# valoohj.net
KiCad netlist of a schematic drawn in EAGLE
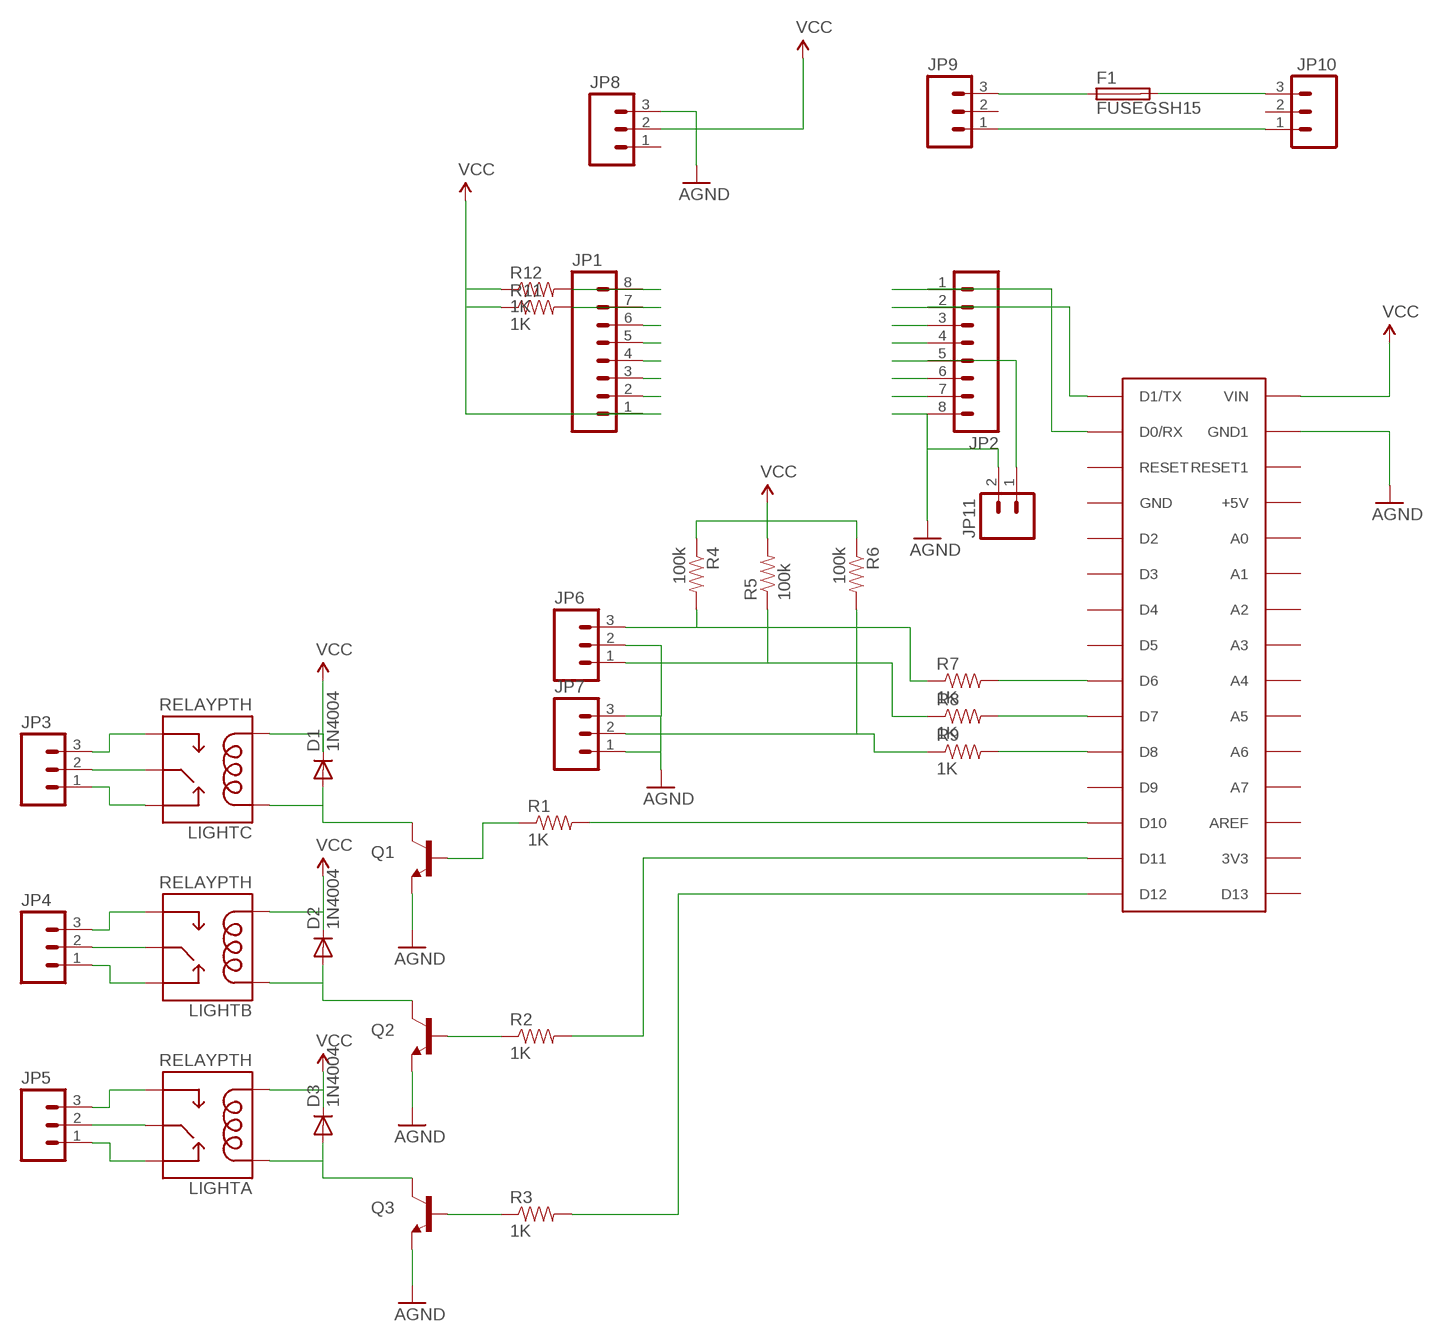
[diagram p0: schematic, sheet 1]

(export (version "E")
  (design (tool "Eeschema 10.0.6"))
  (components
    (comp (ref "D1")
      (value "1N4004")
      (footprint "eagle-import:DO41-10")
      (libsource (lib "eagle-import") (part "1N4004"))
    )
    (comp (ref "D2")
      (value "1N4004")
      (footprint "eagle-import:DO41-10")
      (libsource (lib "eagle-import") (part "1N4004"))
    )
    (comp (ref "D3")
      (value "1N4004")
      (footprint "eagle-import:DO41-10")
      (libsource (lib "eagle-import") (part "1N4004"))
    )
    (comp (ref "F1")
      (value "FUSEGSH15")
      (footprint "eagle-import:GSH15")
      (libsource (lib "eagle-import") (part "FUSEGSH15"))
    )
    (comp (ref "JP1")
      (value "M08LONGPADS")
      (footprint "eagle-import:1X08_LONGPADS")
      (libsource (lib "eagle-import") (part "M08LONGPADS"))
    )
    (comp (ref "JP2")
      (value "M08LONGPADS")
      (footprint "eagle-import:1X08_LONGPADS")
      (libsource (lib "eagle-import") (part "M08LONGPADS"))
    )
    (comp (ref "JP3")
      (value "M03-SCREW-5MM")
      (footprint "eagle-import:SCREWTERMINAL-5MM-3")
      (libsource (lib "eagle-import") (part "M03-SCREW-5MM"))
    )
    (comp (ref "JP4")
      (value "M03-SCREW-5MM")
      (footprint "eagle-import:SCREWTERMINAL-5MM-3")
      (libsource (lib "eagle-import") (part "M03-SCREW-5MM"))
    )
    (comp (ref "JP5")
      (value "M03-SCREW-5MM")
      (footprint "eagle-import:SCREWTERMINAL-5MM-3")
      (libsource (lib "eagle-import") (part "M03-SCREW-5MM"))
    )
    (comp (ref "JP6")
      (value "M03-SCREW-5MM")
      (footprint "eagle-import:SCREWTERMINAL-5MM-3")
      (libsource (lib "eagle-import") (part "M03-SCREW-5MM"))
    )
    (comp (ref "JP7")
      (value "M03-SCREW-5MM")
      (footprint "eagle-import:SCREWTERMINAL-5MM-3")
      (libsource (lib "eagle-import") (part "M03-SCREW-5MM"))
    )
    (comp (ref "JP8")
      (value "M03SCREW")
      (footprint "eagle-import:SCREWTERMINAL-3.5MM-3")
      (libsource (lib "eagle-import") (part "M03SCREW"))
    )
    (comp (ref "JP9")
      (value "M03SCREW")
      (footprint "eagle-import:SCREWTERMINAL-3.5MM-3")
      (libsource (lib "eagle-import") (part "M03SCREW"))
    )
    (comp (ref "JP10")
      (value "M03SCREW")
      (footprint "eagle-import:SCREWTERMINAL-3.5MM-3")
      (libsource (lib "eagle-import") (part "M03SCREW"))
    )
    (comp (ref "JP11")
      (value "M02LOCK")
      (footprint "eagle-import:1X02_LOCK")
      (libsource (lib "eagle-import") (part "M02LOCK"))
    )
    (comp (ref "LIGHTA")
      (value "RELAYPTH")
      (footprint "eagle-import:SRD-05VDC-SL-C")
      (libsource (lib "eagle-import") (part "RELAYPTH"))
    )
    (comp (ref "LIGHTB")
      (value "RELAYPTH")
      (footprint "eagle-import:SRD-05VDC-SL-C")
      (libsource (lib "eagle-import") (part "RELAYPTH"))
    )
    (comp (ref "LIGHTC")
      (value "RELAYPTH")
      (footprint "eagle-import:SRD-05VDC-SL-C")
      (libsource (lib "eagle-import") (part "RELAYPTH"))
    )
    (comp (ref "Q1")
      (value "TRANSISTOR_NPNBC547")
      (footprint "eagle-import:TO-92-AMMO")
      (libsource (lib "eagle-import") (part "TRANSISTOR_NPNBC547"))
    )
    (comp (ref "Q2")
      (value "TRANSISTOR_NPNBC547")
      (footprint "eagle-import:TO-92-AMMO")
      (libsource (lib "eagle-import") (part "TRANSISTOR_NPNBC547"))
    )
    (comp (ref "Q3")
      (value "TRANSISTOR_NPNBC547")
      (footprint "eagle-import:TO-92-AMMO")
      (libsource (lib "eagle-import") (part "TRANSISTOR_NPNBC547"))
    )
    (comp (ref "R1")
      (value "1K")
      (footprint "eagle-import:AXIAL-0.3")
      (libsource (lib "eagle-import") (part "1KOHM-1/4W-1%(PTH)"))
    )
    (comp (ref "R2")
      (value "1K")
      (footprint "eagle-import:AXIAL-0.3")
      (libsource (lib "eagle-import") (part "1KOHM-1/4W-1%(PTH)"))
    )
    (comp (ref "R3")
      (value "1K")
      (footprint "eagle-import:AXIAL-0.3")
      (libsource (lib "eagle-import") (part "1KOHM-1/4W-1%(PTH)"))
    )
    (comp (ref "R4")
      (value "100k")
      (footprint "eagle-import:AXIAL-0.3")
      (libsource (lib "eagle-import") (part "1KOHM-1/4W-1%(PTH)"))
    )
    (comp (ref "R5")
      (value "100k")
      (footprint "eagle-import:AXIAL-0.3")
      (libsource (lib "eagle-import") (part "1KOHM-1/4W-1%(PTH)"))
    )
    (comp (ref "R6")
      (value "100k")
      (footprint "eagle-import:AXIAL-0.3")
      (libsource (lib "eagle-import") (part "1KOHM-1/4W-1%(PTH)"))
    )
    (comp (ref "R7")
      (value "1K")
      (footprint "eagle-import:AXIAL-0.3")
      (libsource (lib "eagle-import") (part "1KOHM-1/4W-1%(PTH)"))
    )
    (comp (ref "R8")
      (value "1K")
      (footprint "eagle-import:AXIAL-0.3")
      (libsource (lib "eagle-import") (part "1KOHM-1/4W-1%(PTH)"))
    )
    (comp (ref "R9")
      (value "1K")
      (footprint "eagle-import:AXIAL-0.3")
      (libsource (lib "eagle-import") (part "1KOHM-1/4W-1%(PTH)"))
    )
    (comp (ref "R11")
      (value "1K")
      (footprint "eagle-import:AXIAL-0.3")
      (libsource (lib "eagle-import") (part "1KOHM-1/4W-1%(PTH)"))
    )
    (comp (ref "R12")
      (value "1K")
      (footprint "eagle-import:AXIAL-0.3")
      (libsource (lib "eagle-import") (part "1KOHM-1/4W-1%(PTH)"))
    )
    (comp (ref "U$2")
      (value "ARDUINONANO")
      (footprint "eagle-import:PDIP-32")
      (libsource (lib "eagle-import") (part "ARDUINONANO"))
    )
  )
  (nets
    (net (code "1") (name "AGND") (class "Default")
      (node (ref "JP11") (pin "2") (pinfunction "2_2") (pintype "passive"))
      (node (ref "JP2") (pin "8") (pinfunction "8_8") (pintype "passive"))
      (node (ref "JP6") (pin "2") (pinfunction "2_2") (pintype "passive"))
      (node (ref "JP7") (pin "1") (pinfunction "1_1") (pintype "passive"))
      (node (ref "JP7") (pin "3") (pinfunction "3_3") (pintype "passive"))
      (node (ref "JP8") (pin "3") (pinfunction "3_3") (pintype "passive"))
      (node (ref "Q1") (pin "3") (pinfunction "E_3") (pintype "passive"))
      (node (ref "Q2") (pin "3") (pinfunction "E_3") (pintype "passive"))
      (node (ref "Q3") (pin "3") (pinfunction "E_3") (pintype "passive"))
      (node (ref "U$2") (pin "GND1") (pinfunction "GND1_GND1") (pintype "bidirectional"))
    )
    (net (code "2") (name "Net-(F1-Pad1)") (class "Default")
      (node (ref "F1") (pin "1") (pinfunction "1_1") (pintype "passive"))
      (node (ref "JP9") (pin "3") (pinfunction "3_3") (pintype "passive"))
    )
    (net (code "3") (name "Net-(F1-Pad2)") (class "Default")
      (node (ref "F1") (pin "2") (pinfunction "2_2") (pintype "passive"))
      (node (ref "JP10") (pin "3") (pinfunction "3_3") (pintype "passive"))
    )
    (net (code "4") (name "Net-(JP2-Pad1)") (class "Default")
      (node (ref "JP2") (pin "1") (pinfunction "1_1") (pintype "passive"))
      (node (ref "U$2") (pin "D0/RX") (pinfunction "D0/RX_D0/RX") (pintype "bidirectional"))
    )
    (net (code "5") (name "Net-(JP2-Pad2)") (class "Default")
      (node (ref "JP2") (pin "2") (pinfunction "2_2") (pintype "passive"))
      (node (ref "U$2") (pin "D1/TX") (pinfunction "D1/TX_D1/TX") (pintype "bidirectional"))
    )
    (net (code "6") (name "Net-(JP3-Pad2)") (class "Default")
      (node (ref "JP3") (pin "2") (pinfunction "2_2") (pintype "passive"))
      (node (ref "LIGHTC") (pin "SWCOMMON") (pinfunction "SWCOMMON_SWCOMMON") (pintype "bidirectional"))
    )
    (net (code "7") (name "Net-(JP3-Pad3)") (class "Default")
      (node (ref "JP3") (pin "3") (pinfunction "3_3") (pintype "passive"))
      (node (ref "LIGHTC") (pin "SWOPEN") (pinfunction "SWOPEN_SWOPEN") (pintype "bidirectional"))
    )
    (net (code "8") (name "Net-(JP4-Pad2)") (class "Default")
      (node (ref "JP4") (pin "2") (pinfunction "2_2") (pintype "passive"))
      (node (ref "LIGHTB") (pin "SWCOMMON") (pinfunction "SWCOMMON_SWCOMMON") (pintype "bidirectional"))
    )
    (net (code "9") (name "Net-(JP4-Pad3)") (class "Default")
      (node (ref "JP4") (pin "3") (pinfunction "3_3") (pintype "passive"))
      (node (ref "LIGHTB") (pin "SWOPEN") (pinfunction "SWOPEN_SWOPEN") (pintype "bidirectional"))
    )
    (net (code "10") (name "Net-(JP5-Pad2)") (class "Default")
      (node (ref "JP5") (pin "2") (pinfunction "2_2") (pintype "passive"))
      (node (ref "LIGHTA") (pin "SWCOMMON") (pinfunction "SWCOMMON_SWCOMMON") (pintype "bidirectional"))
    )
    (net (code "11") (name "Net-(JP5-Pad3)") (class "Default")
      (node (ref "JP5") (pin "3") (pinfunction "3_3") (pintype "passive"))
      (node (ref "LIGHTA") (pin "SWOPEN") (pinfunction "SWOPEN_SWOPEN") (pintype "bidirectional"))
    )
    (net (code "12") (name "Net-(JP10-Pad1)") (class "Default")
      (node (ref "JP10") (pin "1") (pinfunction "1_1") (pintype "passive"))
      (node (ref "JP9") (pin "1") (pinfunction "1_1") (pintype "passive"))
    )
    (net (code "13") (name "Net-(JP11-Pad1)") (class "Default")
      (node (ref "JP11") (pin "1") (pinfunction "1_1") (pintype "passive"))
      (node (ref "JP2") (pin "5") (pinfunction "5_5") (pintype "passive"))
    )
    (net (code "14") (name "Net-(LIGHTA-SWCLOSE)") (class "Default")
      (node (ref "JP5") (pin "1") (pinfunction "1_1") (pintype "passive"))
      (node (ref "LIGHTA") (pin "SWCLOSED") (pinfunction "SWCLOSE_SWCLOSED") (pintype "bidirectional"))
    )
    (net (code "15") (name "Net-(LIGHTB-SWCLOSE)") (class "Default")
      (node (ref "JP4") (pin "1") (pinfunction "1_1") (pintype "passive"))
      (node (ref "LIGHTB") (pin "SWCLOSED") (pinfunction "SWCLOSE_SWCLOSED") (pintype "bidirectional"))
    )
    (net (code "16") (name "Net-(LIGHTC-SWCLOSE)") (class "Default")
      (node (ref "JP3") (pin "1") (pinfunction "1_1") (pintype "passive"))
      (node (ref "LIGHTC") (pin "SWCLOSED") (pinfunction "SWCLOSE_SWCLOSED") (pintype "bidirectional"))
    )
    (net (code "17") (name "Net-(Q1-B)") (class "Default")
      (node (ref "Q1") (pin "2") (pinfunction "B_2") (pintype "passive"))
      (node (ref "R1") (pin "P$1") (pinfunction "1_P$1") (pintype "passive"))
    )
    (net (code "18") (name "Net-(Q1-C)") (class "Default")
      (node (ref "D1") (pin "A") (pinfunction "A_A") (pintype "passive"))
      (node (ref "LIGHTC") (pin "COIL1") (pinfunction "COIL1_COIL1") (pintype "bidirectional"))
      (node (ref "Q1") (pin "1") (pinfunction "C_1") (pintype "passive"))
    )
    (net (code "19") (name "Net-(Q2-B)") (class "Default")
      (node (ref "Q2") (pin "2") (pinfunction "B_2") (pintype "passive"))
      (node (ref "R2") (pin "P$1") (pinfunction "1_P$1") (pintype "passive"))
    )
    (net (code "20") (name "Net-(Q2-C)") (class "Default")
      (node (ref "D2") (pin "A") (pinfunction "A_A") (pintype "passive"))
      (node (ref "LIGHTB") (pin "COIL1") (pinfunction "COIL1_COIL1") (pintype "bidirectional"))
      (node (ref "Q2") (pin "1") (pinfunction "C_1") (pintype "passive"))
    )
    (net (code "21") (name "Net-(Q3-B)") (class "Default")
      (node (ref "Q3") (pin "2") (pinfunction "B_2") (pintype "passive"))
      (node (ref "R3") (pin "P$1") (pinfunction "1_P$1") (pintype "passive"))
    )
    (net (code "22") (name "Net-(Q3-C)") (class "Default")
      (node (ref "D3") (pin "A") (pinfunction "A_A") (pintype "passive"))
      (node (ref "LIGHTA") (pin "COIL1") (pinfunction "COIL1_COIL1") (pintype "bidirectional"))
      (node (ref "Q3") (pin "1") (pinfunction "C_1") (pintype "passive"))
    )
    (net (code "23") (name "Net-(R1-2)") (class "Default")
      (node (ref "R1") (pin "P$2") (pinfunction "2_P$2") (pintype "passive"))
      (node (ref "U$2") (pin "D10") (pinfunction "D10_D10") (pintype "bidirectional"))
    )
    (net (code "24") (name "Net-(R2-2)") (class "Default")
      (node (ref "R2") (pin "P$2") (pinfunction "2_P$2") (pintype "passive"))
      (node (ref "U$2") (pin "D11") (pinfunction "D11_D11") (pintype "bidirectional"))
    )
    (net (code "25") (name "Net-(R3-2)") (class "Default")
      (node (ref "R3") (pin "P$2") (pinfunction "2_P$2") (pintype "passive"))
      (node (ref "U$2") (pin "D12") (pinfunction "D12_D12") (pintype "bidirectional"))
    )
    (net (code "26") (name "Net-(R4-2)") (class "Default")
      (node (ref "JP6") (pin "3") (pinfunction "3_3") (pintype "passive"))
      (node (ref "R4") (pin "P$2") (pinfunction "2_P$2") (pintype "passive"))
      (node (ref "R7") (pin "P$1") (pinfunction "1_P$1") (pintype "passive"))
    )
    (net (code "27") (name "Net-(R5-1)") (class "Default")
      (node (ref "JP6") (pin "1") (pinfunction "1_1") (pintype "passive"))
      (node (ref "R5") (pin "P$1") (pinfunction "1_P$1") (pintype "passive"))
      (node (ref "R8") (pin "P$1") (pinfunction "1_P$1") (pintype "passive"))
    )
    (net (code "28") (name "Net-(R6-2)") (class "Default")
      (node (ref "JP7") (pin "2") (pinfunction "2_2") (pintype "passive"))
      (node (ref "R6") (pin "P$2") (pinfunction "2_P$2") (pintype "passive"))
      (node (ref "R9") (pin "P$1") (pinfunction "1_P$1") (pintype "passive"))
    )
    (net (code "29") (name "Net-(R7-2)") (class "Default")
      (node (ref "R7") (pin "P$2") (pinfunction "2_P$2") (pintype "passive"))
      (node (ref "U$2") (pin "D6") (pinfunction "D6_D6") (pintype "bidirectional"))
    )
    (net (code "30") (name "Net-(R8-2)") (class "Default")
      (node (ref "R8") (pin "P$2") (pinfunction "2_P$2") (pintype "passive"))
      (node (ref "U$2") (pin "D7") (pinfunction "D7_D7") (pintype "bidirectional"))
    )
    (net (code "31") (name "Net-(R9-2)") (class "Default")
      (node (ref "R9") (pin "P$2") (pinfunction "2_P$2") (pintype "passive"))
      (node (ref "U$2") (pin "D8") (pinfunction "D8_D8") (pintype "bidirectional"))
    )
    (net (code "32") (name "Net-(R11-2)") (class "Default")
      (node (ref "JP1") (pin "7") (pinfunction "7_7") (pintype "passive"))
      (node (ref "R11") (pin "P$2") (pinfunction "2_P$2") (pintype "passive"))
    )
    (net (code "33") (name "Net-(R12-2)") (class "Default")
      (node (ref "JP1") (pin "8") (pinfunction "8_8") (pintype "passive"))
      (node (ref "R12") (pin "P$2") (pinfunction "2_P$2") (pintype "passive"))
    )
    (net (code "34") (name "VCC") (class "Default")
      (node (ref "D1") (pin "C") (pinfunction "C_C") (pintype "passive"))
      (node (ref "D2") (pin "C") (pinfunction "C_C") (pintype "passive"))
      (node (ref "D3") (pin "C") (pinfunction "C_C") (pintype "passive"))
      (node (ref "JP1") (pin "1") (pinfunction "1_1") (pintype "passive"))
      (node (ref "JP8") (pin "2") (pinfunction "2_2") (pintype "passive"))
      (node (ref "LIGHTA") (pin "COIL0") (pinfunction "COIL0_COIL0") (pintype "bidirectional"))
      (node (ref "LIGHTB") (pin "COIL0") (pinfunction "COIL0_COIL0") (pintype "bidirectional"))
      (node (ref "LIGHTC") (pin "COIL0") (pinfunction "COIL0_COIL0") (pintype "bidirectional"))
      (node (ref "R11") (pin "P$1") (pinfunction "1_P$1") (pintype "passive"))
      (node (ref "R12") (pin "P$1") (pinfunction "1_P$1") (pintype "passive"))
      (node (ref "R4") (pin "P$1") (pinfunction "1_P$1") (pintype "passive"))
      (node (ref "R5") (pin "P$2") (pinfunction "2_P$2") (pintype "passive"))
      (node (ref "R6") (pin "P$1") (pinfunction "1_P$1") (pintype "passive"))
      (node (ref "U$2") (pin "VIN") (pinfunction "VIN_VIN") (pintype "bidirectional"))
    )
    (net (code "35") (name "unconnected-(JP1-Pad2)") (class "Default")
      (node (ref "JP1") (pin "2") (pinfunction "2_2") (pintype "passive"))
    )
    (net (code "36") (name "unconnected-(JP1-Pad3)") (class "Default")
      (node (ref "JP1") (pin "3") (pinfunction "3_3") (pintype "passive"))
    )
    (net (code "37") (name "unconnected-(JP1-Pad4)") (class "Default")
      (node (ref "JP1") (pin "4") (pinfunction "4_4") (pintype "passive"))
    )
    (net (code "38") (name "unconnected-(JP1-Pad5)") (class "Default")
      (node (ref "JP1") (pin "5") (pinfunction "5_5") (pintype "passive"))
    )
    (net (code "39") (name "unconnected-(JP1-Pad6)") (class "Default")
      (node (ref "JP1") (pin "6") (pinfunction "6_6") (pintype "passive"))
    )
    (net (code "40") (name "unconnected-(JP2-Pad3)") (class "Default")
      (node (ref "JP2") (pin "3") (pinfunction "3_3") (pintype "passive"))
    )
    (net (code "41") (name "unconnected-(JP2-Pad4)") (class "Default")
      (node (ref "JP2") (pin "4") (pinfunction "4_4") (pintype "passive"))
    )
    (net (code "42") (name "unconnected-(JP2-Pad6)") (class "Default")
      (node (ref "JP2") (pin "6") (pinfunction "6_6") (pintype "passive"))
    )
    (net (code "43") (name "unconnected-(JP2-Pad7)") (class "Default")
      (node (ref "JP2") (pin "7") (pinfunction "7_7") (pintype "passive"))
    )
    (net (code "44") (name "unconnected-(JP8-Pad1)") (class "Default")
      (node (ref "JP8") (pin "1") (pinfunction "1_1") (pintype "passive"))
    )
    (net (code "45") (name "unconnected-(JP9-Pad2)") (class "Default")
      (node (ref "JP9") (pin "2") (pinfunction "2_2") (pintype "passive"))
    )
    (net (code "46") (name "unconnected-(JP10-Pad2)") (class "Default")
      (node (ref "JP10") (pin "2") (pinfunction "2_2") (pintype "passive"))
    )
    (net (code "47") (name "unconnected-(U$2-Pad+5V)") (class "Default")
      (node (ref "U$2") (pin "+5V") (pinfunction "+5V_+5V") (pintype "bidirectional"))
    )
    (net (code "48") (name "unconnected-(U$2-Pad3V3)") (class "Default")
      (node (ref "U$2") (pin "3V3") (pinfunction "3V3_3V3") (pintype "bidirectional"))
    )
    (net (code "49") (name "unconnected-(U$2-PadA0)") (class "Default")
      (node (ref "U$2") (pin "A0") (pinfunction "A0_A0") (pintype "bidirectional"))
    )
    (net (code "50") (name "unconnected-(U$2-PadA1)") (class "Default")
      (node (ref "U$2") (pin "A1") (pinfunction "A1_A1") (pintype "bidirectional"))
    )
    (net (code "51") (name "unconnected-(U$2-PadA2)") (class "Default")
      (node (ref "U$2") (pin "A2") (pinfunction "A2_A2") (pintype "bidirectional"))
    )
    (net (code "52") (name "unconnected-(U$2-PadA3)") (class "Default")
      (node (ref "U$2") (pin "A3") (pinfunction "A3_A3") (pintype "bidirectional"))
    )
    (net (code "53") (name "unconnected-(U$2-PadA4)") (class "Default")
      (node (ref "U$2") (pin "A4") (pinfunction "A4_A4") (pintype "bidirectional"))
    )
    (net (code "54") (name "unconnected-(U$2-PadA5)") (class "Default")
      (node (ref "U$2") (pin "A5") (pinfunction "A5_A5") (pintype "bidirectional"))
    )
    (net (code "55") (name "unconnected-(U$2-PadA6)") (class "Default")
      (node (ref "U$2") (pin "A6") (pinfunction "A6_A6") (pintype "bidirectional"))
    )
    (net (code "56") (name "unconnected-(U$2-PadA7)") (class "Default")
      (node (ref "U$2") (pin "A7") (pinfunction "A7_A7") (pintype "bidirectional"))
    )
    (net (code "57") (name "unconnected-(U$2-PadAREF)") (class "Default")
      (node (ref "U$2") (pin "AREF") (pinfunction "AREF_AREF") (pintype "bidirectional"))
    )
    (net (code "58") (name "unconnected-(U$2-PadD2)") (class "Default")
      (node (ref "U$2") (pin "D2") (pinfunction "D2_D2") (pintype "bidirectional"))
    )
    (net (code "59") (name "unconnected-(U$2-PadD3)") (class "Default")
      (node (ref "U$2") (pin "D3") (pinfunction "D3_D3") (pintype "bidirectional"))
    )
    (net (code "60") (name "unconnected-(U$2-PadD4)") (class "Default")
      (node (ref "U$2") (pin "D4") (pinfunction "D4_D4") (pintype "bidirectional"))
    )
    (net (code "61") (name "unconnected-(U$2-PadD5)") (class "Default")
      (node (ref "U$2") (pin "D5") (pinfunction "D5_D5") (pintype "bidirectional"))
    )
    (net (code "62") (name "unconnected-(U$2-PadD9)") (class "Default")
      (node (ref "U$2") (pin "D9") (pinfunction "D9_D9") (pintype "bidirectional"))
    )
    (net (code "63") (name "unconnected-(U$2-PadD13)") (class "Default")
      (node (ref "U$2") (pin "D13") (pinfunction "D13_D13") (pintype "bidirectional"))
    )
    (net (code "64") (name "unconnected-(U$2-PadGND)") (class "Default")
      (node (ref "U$2") (pin "GND") (pinfunction "GND_GND") (pintype "bidirectional"))
    )
    (net (code "65") (name "unconnected-(U$2-PadRESET)") (class "Default")
      (node (ref "U$2") (pin "RESET") (pinfunction "RESET_RESET") (pintype "bidirectional"))
    )
    (net (code "66") (name "unconnected-(U$2-PadRESET1)") (class "Default")
      (node (ref "U$2") (pin "RESET1") (pinfunction "RESET1_RESET1") (pintype "bidirectional"))
    )
  )
)
